# Croduino_Pico.net
KiCad netlist of a schematic drawn in EAGLE
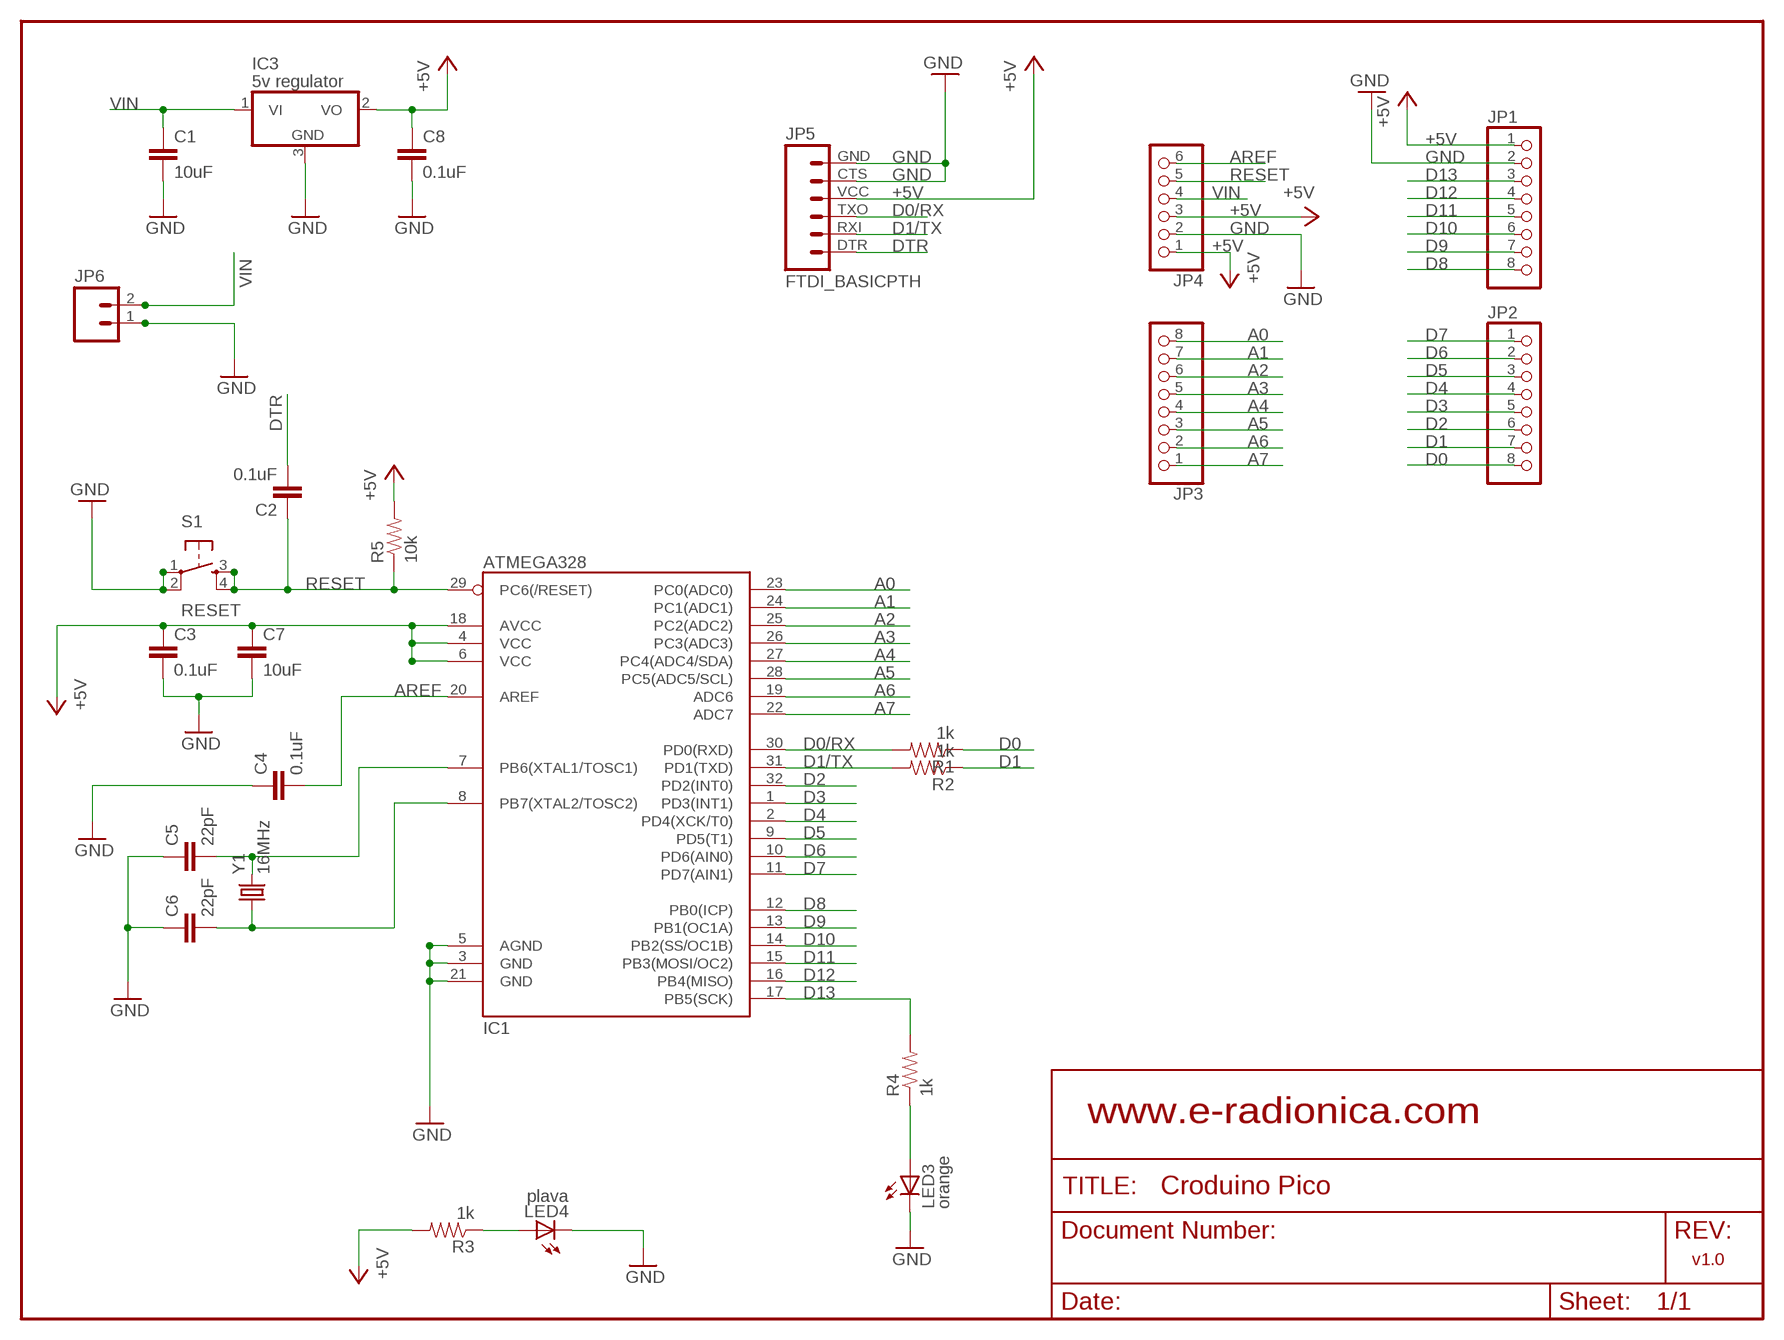
[diagram p0: schematic, sheet 1]

(export (version "E")
  (design (tool "Eeschema 10.0.6"))
  (components
    (comp (ref "C1")
      (value "10uF")
      (footprint "eagle-import:C3216")
      (libsource (lib "eagle-import") (part "C-EUC3216"))
    )
    (comp (ref "C2")
      (value "0.1uF")
      (footprint "eagle-import:0603-CAP")
      (libsource (lib "eagle-import") (part "CAP0603-CAP"))
    )
    (comp (ref "C3")
      (value "0.1uF")
      (footprint "eagle-import:0603-CAP")
      (libsource (lib "eagle-import") (part "CAP0603-CAP"))
    )
    (comp (ref "C4")
      (value "0.1uF")
      (footprint "eagle-import:0603-CAP")
      (libsource (lib "eagle-import") (part "CAP0603-CAP"))
    )
    (comp (ref "C5")
      (value "22pF")
      (footprint "eagle-import:0603-CAP")
      (libsource (lib "eagle-import") (part "CAP0603-CAP"))
    )
    (comp (ref "C6")
      (value "22pF")
      (footprint "eagle-import:0603-CAP")
      (libsource (lib "eagle-import") (part "CAP0603-CAP"))
    )
    (comp (ref "C7")
      (value "10uF")
      (footprint "eagle-import:C3216")
      (libsource (lib "eagle-import") (part "C-EUC3216"))
    )
    (comp (ref "C8")
      (value "0.1uF")
      (footprint "eagle-import:0603-CAP")
      (libsource (lib "eagle-import") (part "CAP0603-CAP"))
    )
    (comp (ref "IC1")
      (value "ATMEGA328")
      (footprint "eagle-import:TQFP32-08")
      (libsource (lib "eagle-import") (part "ATMEGA168"))
    )
    (comp (ref "IC3")
      (value "5v regulator")
      (footprint "eagle-import:TO252")
      (libsource (lib "eagle-import") (part "78DT05"))
    )
    (comp (ref "JP1")
      (value "PINHD-1X8BIG")
      (footprint "eagle-import:1X08-BIG")
      (libsource (lib "eagle-import") (part "PINHD-1X8BIG"))
    )
    (comp (ref "JP2")
      (value "PINHD-1X8BIG")
      (footprint "eagle-import:1X08-BIG")
      (libsource (lib "eagle-import") (part "PINHD-1X8BIG"))
    )
    (comp (ref "JP3")
      (value "PINHD-1X8BIG")
      (footprint "eagle-import:1X08-BIG")
      (libsource (lib "eagle-import") (part "PINHD-1X8BIG"))
    )
    (comp (ref "JP4")
      (value "PINHD-1X6B")
      (footprint "eagle-import:1X06-BIG")
      (libsource (lib "eagle-import") (part "PINHD-1X6B"))
    )
    (comp (ref "JP5")
      (value "FTDI_BASICPTH")
      (footprint "eagle-import:FTDI_BASIC")
      (libsource (lib "eagle-import") (part "FTDI_BASICPTH"))
    )
    (comp (ref "JP6")
      (value "M02LOCK_LONGPADS")
      (footprint "eagle-import:1X02_LOCK_LONGPADS")
      (libsource (lib "eagle-import") (part "M02LOCK_LONGPADS"))
    )
    (comp (ref "LED3")
      (value "orange")
      (footprint "eagle-import:CHIP-LED0805")
      (libsource (lib "eagle-import") (part "LEDCHIP-LED0805"))
    )
    (comp (ref "LED4")
      (value "plava")
      (footprint "eagle-import:CHIP-LED0805")
      (libsource (lib "eagle-import") (part "LEDCHIP-LED0805"))
    )
    (comp (ref "R1")
      (value "1k")
      (footprint "eagle-import:0603-RES")
      (libsource (lib "eagle-import") (part "RESISTOR0603-RES"))
    )
    (comp (ref "R2")
      (value "1k")
      (footprint "eagle-import:0603-RES")
      (libsource (lib "eagle-import") (part "RESISTOR0603-RES"))
    )
    (comp (ref "R3")
      (value "1k")
      (footprint "eagle-import:0603-RES")
      (libsource (lib "eagle-import") (part "RESISTOR0603-RES"))
    )
    (comp (ref "R4")
      (value "1k")
      (footprint "eagle-import:0603-RES")
      (libsource (lib "eagle-import") (part "RESISTOR0603-RES"))
    )
    (comp (ref "R5")
      (value "10k")
      (footprint "eagle-import:0603-RES")
      (libsource (lib "eagle-import") (part "RESISTOR0603-RES"))
    )
    (comp (ref "S1")
      (value "RESET")
      (footprint "eagle-import:TACTILE_SWITCH_SMD")
      (libsource (lib "eagle-import") (part "TAC_SWITCHSMD"))
    )
    (comp (ref "Y1")
      (value "16MHz")
      (footprint "eagle-import:CRYSTAL-SMD-5X3")
      (libsource (lib "eagle-import") (part "CRYSTAL5X3"))
    )
  )
  (nets
    (net (code "1") (name "+5V") (class "Default")
      (node (ref "C3") (pin "1") (pinfunction "1_1") (pintype "passive"))
      (node (ref "C7") (pin "1") (pinfunction "1_1") (pintype "passive"))
      (node (ref "C8") (pin "1") (pinfunction "1_1") (pintype "passive"))
      (node (ref "IC1") (pin "18") (pinfunction "AVCC_18") (pintype "bidirectional"))
      (node (ref "IC1") (pin "4") (pinfunction "VCC_4") (pintype "bidirectional"))
      (node (ref "IC1") (pin "6") (pinfunction "VCC_6") (pintype "bidirectional"))
      (node (ref "IC3") (pin "2") (pinfunction "VO_2") (pintype "passive"))
      (node (ref "JP1") (pin "1") (pinfunction "1_1") (pintype "passive"))
      (node (ref "JP4") (pin "1") (pinfunction "1_1") (pintype "passive"))
      (node (ref "JP4") (pin "3") (pinfunction "3_3") (pintype "passive"))
      (node (ref "JP5") (pin "VCC") (pinfunction "4_VCC") (pintype "passive"))
      (node (ref "R3") (pin "2") (pinfunction "2_2") (pintype "passive"))
      (node (ref "R5") (pin "2") (pinfunction "2_2") (pintype "passive"))
    )
    (net (code "2") (name "/A0") (class "Default")
      (node (ref "IC1") (pin "23") (pinfunction "PC0(ADC0)_23") (pintype "bidirectional"))
      (node (ref "JP3") (pin "8") (pinfunction "8_8") (pintype "passive"))
    )
    (net (code "3") (name "/A1") (class "Default")
      (node (ref "IC1") (pin "24") (pinfunction "PC1(ADC1)_24") (pintype "bidirectional"))
      (node (ref "JP3") (pin "7") (pinfunction "7_7") (pintype "passive"))
    )
    (net (code "4") (name "/A2") (class "Default")
      (node (ref "IC1") (pin "25") (pinfunction "PC2(ADC2)_25") (pintype "bidirectional"))
      (node (ref "JP3") (pin "6") (pinfunction "6_6") (pintype "passive"))
    )
    (net (code "5") (name "/A3") (class "Default")
      (node (ref "IC1") (pin "26") (pinfunction "PC3(ADC3)_26") (pintype "bidirectional"))
      (node (ref "JP3") (pin "5") (pinfunction "5_5") (pintype "passive"))
    )
    (net (code "6") (name "/A4") (class "Default")
      (node (ref "IC1") (pin "27") (pinfunction "PC4(ADC4/SDA)_27") (pintype "bidirectional"))
      (node (ref "JP3") (pin "4") (pinfunction "4_4") (pintype "passive"))
    )
    (net (code "7") (name "/A5") (class "Default")
      (node (ref "IC1") (pin "28") (pinfunction "PC5(ADC5/SCL)_28") (pintype "bidirectional"))
      (node (ref "JP3") (pin "3") (pinfunction "3_3") (pintype "passive"))
    )
    (net (code "8") (name "/A6") (class "Default")
      (node (ref "IC1") (pin "19") (pinfunction "ADC6_19") (pintype "bidirectional"))
      (node (ref "JP3") (pin "2") (pinfunction "2_2") (pintype "passive"))
    )
    (net (code "9") (name "/A7") (class "Default")
      (node (ref "IC1") (pin "22") (pinfunction "ADC7_22") (pintype "bidirectional"))
      (node (ref "JP3") (pin "1") (pinfunction "1_1") (pintype "passive"))
    )
    (net (code "10") (name "/AREF") (class "Default")
      (node (ref "C4") (pin "2") (pinfunction "2_2") (pintype "passive"))
      (node (ref "IC1") (pin "20") (pinfunction "AREF_20") (pintype "bidirectional"))
      (node (ref "JP4") (pin "6") (pinfunction "6_6") (pintype "passive"))
    )
    (net (code "11") (name "/D0") (class "Default")
      (node (ref "JP2") (pin "8") (pinfunction "8_8") (pintype "passive"))
      (node (ref "R1") (pin "1") (pinfunction "1_1") (pintype "passive"))
    )
    (net (code "12") (name "/D0{slash}RX") (class "Default")
      (node (ref "IC1") (pin "30") (pinfunction "PD0(RXD)_30") (pintype "bidirectional"))
      (node (ref "JP5") (pin "TXO") (pinfunction "3_TXO") (pintype "passive"))
      (node (ref "R1") (pin "2") (pinfunction "2_2") (pintype "passive"))
    )
    (net (code "13") (name "/D1") (class "Default")
      (node (ref "JP2") (pin "7") (pinfunction "7_7") (pintype "passive"))
      (node (ref "R2") (pin "1") (pinfunction "1_1") (pintype "passive"))
    )
    (net (code "14") (name "/D1{slash}TX") (class "Default")
      (node (ref "IC1") (pin "31") (pinfunction "PD1(TXD)_31") (pintype "bidirectional"))
      (node (ref "JP5") (pin "RXI") (pinfunction "2_RXI") (pintype "passive"))
      (node (ref "R2") (pin "2") (pinfunction "2_2") (pintype "passive"))
    )
    (net (code "15") (name "/D2") (class "Default")
      (node (ref "IC1") (pin "32") (pinfunction "PD2(INT0)_32") (pintype "bidirectional"))
      (node (ref "JP2") (pin "6") (pinfunction "6_6") (pintype "passive"))
    )
    (net (code "16") (name "/D3") (class "Default")
      (node (ref "IC1") (pin "1") (pinfunction "PD3(INT1)_1") (pintype "bidirectional"))
      (node (ref "JP2") (pin "5") (pinfunction "5_5") (pintype "passive"))
    )
    (net (code "17") (name "/D4") (class "Default")
      (node (ref "IC1") (pin "2") (pinfunction "PD4(XCK/T0)_2") (pintype "bidirectional"))
      (node (ref "JP2") (pin "4") (pinfunction "4_4") (pintype "passive"))
    )
    (net (code "18") (name "/D5") (class "Default")
      (node (ref "IC1") (pin "9") (pinfunction "PD5(T1)_9") (pintype "bidirectional"))
      (node (ref "JP2") (pin "3") (pinfunction "3_3") (pintype "passive"))
    )
    (net (code "19") (name "/D6") (class "Default")
      (node (ref "IC1") (pin "10") (pinfunction "PD6(AIN0)_10") (pintype "bidirectional"))
      (node (ref "JP2") (pin "2") (pinfunction "2_2") (pintype "passive"))
    )
    (net (code "20") (name "/D7") (class "Default")
      (node (ref "IC1") (pin "11") (pinfunction "PD7(AIN1)_11") (pintype "bidirectional"))
      (node (ref "JP2") (pin "1") (pinfunction "1_1") (pintype "passive"))
    )
    (net (code "21") (name "/D8") (class "Default")
      (node (ref "IC1") (pin "12") (pinfunction "PB0(ICP)_12") (pintype "bidirectional"))
      (node (ref "JP1") (pin "8") (pinfunction "8_8") (pintype "passive"))
    )
    (net (code "22") (name "/D9") (class "Default")
      (node (ref "IC1") (pin "13") (pinfunction "PB1(OC1A)_13") (pintype "bidirectional"))
      (node (ref "JP1") (pin "7") (pinfunction "7_7") (pintype "passive"))
    )
    (net (code "23") (name "/D10") (class "Default")
      (node (ref "IC1") (pin "14") (pinfunction "PB2(SS/OC1B)_14") (pintype "bidirectional"))
      (node (ref "JP1") (pin "6") (pinfunction "6_6") (pintype "passive"))
    )
    (net (code "24") (name "/D11") (class "Default")
      (node (ref "IC1") (pin "15") (pinfunction "PB3(MOSI/OC2)_15") (pintype "bidirectional"))
      (node (ref "JP1") (pin "5") (pinfunction "5_5") (pintype "passive"))
    )
    (net (code "25") (name "/D12") (class "Default")
      (node (ref "IC1") (pin "16") (pinfunction "PB4(MISO)_16") (pintype "bidirectional"))
      (node (ref "JP1") (pin "4") (pinfunction "4_4") (pintype "passive"))
    )
    (net (code "26") (name "/D13") (class "Default")
      (node (ref "IC1") (pin "17") (pinfunction "PB5(SCK)_17") (pintype "bidirectional"))
      (node (ref "JP1") (pin "3") (pinfunction "3_3") (pintype "passive"))
      (node (ref "R4") (pin "2") (pinfunction "2_2") (pintype "passive"))
    )
    (net (code "27") (name "/DTR") (class "Default")
      (node (ref "C2") (pin "2") (pinfunction "2_2") (pintype "passive"))
      (node (ref "JP5") (pin "DTR") (pinfunction "1_DTR") (pintype "passive"))
    )
    (net (code "28") (name "/RESET") (class "Default")
      (node (ref "C2") (pin "1") (pinfunction "1_1") (pintype "passive"))
      (node (ref "IC1") (pin "29") (pinfunction "PC6(/RESET)_29") (pintype "bidirectional"))
      (node (ref "JP4") (pin "5") (pinfunction "5_5") (pintype "passive"))
      (node (ref "R5") (pin "1") (pinfunction "1_1") (pintype "passive"))
      (node (ref "S1") (pin "3") (pinfunction "3_3") (pintype "passive"))
      (node (ref "S1") (pin "4") (pinfunction "4_4") (pintype "passive"))
    )
    (net (code "29") (name "/VIN") (class "Default")
      (node (ref "C1") (pin "1") (pinfunction "1_1") (pintype "passive"))
      (node (ref "IC3") (pin "1") (pinfunction "VI_1") (pintype "input"))
      (node (ref "JP4") (pin "4") (pinfunction "4_4") (pintype "passive"))
      (node (ref "JP6") (pin "2") (pinfunction "2_2") (pintype "passive"))
    )
    (net (code "30") (name "GND") (class "Default")
      (node (ref "C1") (pin "2") (pinfunction "2_2") (pintype "passive"))
      (node (ref "C3") (pin "2") (pinfunction "2_2") (pintype "passive"))
      (node (ref "C4") (pin "1") (pinfunction "1_1") (pintype "passive"))
      (node (ref "C5") (pin "1") (pinfunction "1_1") (pintype "passive"))
      (node (ref "C6") (pin "1") (pinfunction "1_1") (pintype "passive"))
      (node (ref "C7") (pin "2") (pinfunction "2_2") (pintype "passive"))
      (node (ref "C8") (pin "2") (pinfunction "2_2") (pintype "passive"))
      (node (ref "IC1") (pin "21") (pinfunction "GND_21") (pintype "bidirectional"))
      (node (ref "IC1") (pin "3") (pinfunction "GND_3") (pintype "bidirectional"))
      (node (ref "IC1") (pin "5") (pinfunction "AGND_5") (pintype "bidirectional"))
      (node (ref "IC3") (pin "3") (pinfunction "GND_3") (pintype "passive"))
      (node (ref "JP1") (pin "2") (pinfunction "2_2") (pintype "passive"))
      (node (ref "JP4") (pin "2") (pinfunction "2_2") (pintype "passive"))
      (node (ref "JP5") (pin "CTS") (pinfunction "5_CTS") (pintype "passive"))
      (node (ref "JP5") (pin "GND") (pinfunction "6_GND") (pintype "passive"))
      (node (ref "JP6") (pin "1") (pinfunction "1_1") (pintype "passive"))
      (node (ref "LED3") (pin "C") (pinfunction "C_C") (pintype "passive"))
      (node (ref "LED4") (pin "C") (pinfunction "C_C") (pintype "passive"))
      (node (ref "S1") (pin "1") (pinfunction "1_1") (pintype "passive"))
      (node (ref "S1") (pin "2") (pinfunction "2_2") (pintype "passive"))
    )
    (net (code "31") (name "Net-(IC1-PB6(XTAL1{slash}TOSC1))") (class "Default")
      (node (ref "C5") (pin "2") (pinfunction "2_2") (pintype "passive"))
      (node (ref "IC1") (pin "7") (pinfunction "PB6(XTAL1/TOSC1)_7") (pintype "bidirectional"))
      (node (ref "Y1") (pin "3") (pinfunction "2_3") (pintype "passive"))
    )
    (net (code "32") (name "Net-(IC1-PB7(XTAL2{slash}TOSC2))") (class "Default")
      (node (ref "C6") (pin "2") (pinfunction "2_2") (pintype "passive"))
      (node (ref "IC1") (pin "8") (pinfunction "PB7(XTAL2/TOSC2)_8") (pintype "bidirectional"))
      (node (ref "Y1") (pin "1") (pinfunction "1_1") (pintype "passive"))
    )
    (net (code "33") (name "Net-(LED3-PadA)") (class "Default")
      (node (ref "LED3") (pin "A") (pinfunction "A_A") (pintype "passive"))
      (node (ref "R4") (pin "1") (pinfunction "1_1") (pintype "passive"))
    )
    (net (code "34") (name "Net-(LED4-PadA)") (class "Default")
      (node (ref "LED4") (pin "A") (pinfunction "A_A") (pintype "passive"))
      (node (ref "R3") (pin "1") (pinfunction "1_1") (pintype "passive"))
    )
  )
)
